# ChaiNEO_FrontConn_2x3.net
KiCad netlist of a schematic drawn in EAGLE
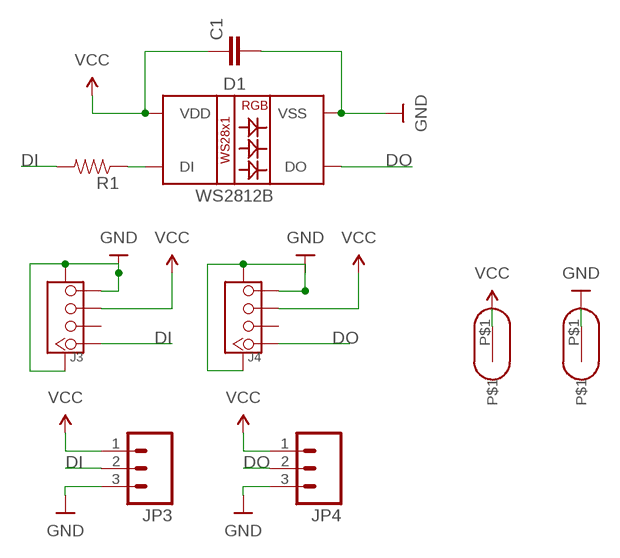
[diagram p0: schematic, sheet 1]

(export (version "E")
  (design (tool "Eeschema 10.0.6"))
  (components
    (comp (ref "C1")
      (value "CAP0603-CAP")
      (footprint "eagle-import:0603-CAP")
      (libsource (lib "eagle-import") (part "CAP0603-CAP"))
    )
    (comp (ref "D1")
      (value "WS2812B")
      (footprint "eagle-import:WS2812B")
      (libsource (lib "eagle-import") (part "WS2812B"))
    )
    (comp (ref "J3")
      (value "TWIG-4P-2.0-SMD-FEMALE-REINFORCE90D")
      (footprint "eagle-import:4P-SMD-2.0-90D")
      (libsource (lib "eagle-import") (part "TWIG-4P-2.0-SMD-FEMALE-REINFORCE90D"))
    )
    (comp (ref "J4")
      (value "TWIG-4P-2.0-SMD-FEMALE-REINFORCE90D")
      (footprint "eagle-import:4P-SMD-2.0-90D")
      (libsource (lib "eagle-import") (part "TWIG-4P-2.0-SMD-FEMALE-REINFORCE90D"))
    )
    (comp (ref "JP3")
      (value "M03LONGPADS")
      (footprint "eagle-import:1X03_LONGPADS")
      (libsource (lib "eagle-import") (part "M03LONGPADS"))
    )
    (comp (ref "JP4")
      (value "M03LONGPADS")
      (footprint "eagle-import:1X03_LONGPADS")
      (libsource (lib "eagle-import") (part "M03LONGPADS"))
    )
    (comp (ref "R1")
      (value "RESISTOR0603-RES")
      (footprint "eagle-import:0603-RES")
      (libsource (lib "eagle-import") (part "RESISTOR0603-RES"))
    )
    (comp (ref "U$7")
      (value "PLATED_TIE_MOUNT")
      (footprint "eagle-import:PLATED_TIE_MOUNT")
      (libsource (lib "eagle-import") (part "PLATED_TIE_MOUNT"))
    )
    (comp (ref "U$8")
      (value "PLATED_TIE_MOUNT")
      (footprint "eagle-import:PLATED_TIE_MOUNT")
      (libsource (lib "eagle-import") (part "PLATED_TIE_MOUNT"))
    )
  )
  (nets
    (net (code "1") (name "/DI") (class "Default")
      (node (ref "J3") (pin "1") (pinfunction "1_1") (pintype "bidirectional"))
      (node (ref "JP3") (pin "2") (pinfunction "2_2") (pintype "passive"))
      (node (ref "R1") (pin "2") (pinfunction "2_2") (pintype "passive"))
    )
    (net (code "2") (name "/DO") (class "Default")
      (node (ref "D1") (pin "2") (pinfunction "DO_2") (pintype "bidirectional"))
      (node (ref "J4") (pin "1") (pinfunction "1_1") (pintype "bidirectional"))
      (node (ref "JP4") (pin "2") (pinfunction "2_2") (pintype "passive"))
    )
    (net (code "3") (name "GND") (class "Default")
      (node (ref "C1") (pin "2") (pinfunction "2_2") (pintype "passive"))
      (node (ref "D1") (pin "3") (pinfunction "VSS_3") (pintype "bidirectional"))
      (node (ref "J3") (pin "4") (pinfunction "4_4") (pintype "bidirectional"))
      (node (ref "J3") (pin "SS1") (pinfunction "SS1_SS1") (pintype "bidirectional"))
      (node (ref "J3") (pin "SS2") (pinfunction "SS2_SS2") (pintype "bidirectional"))
      (node (ref "J4") (pin "4") (pinfunction "4_4") (pintype "bidirectional"))
      (node (ref "J4") (pin "SS1") (pinfunction "SS1_SS1") (pintype "bidirectional"))
      (node (ref "J4") (pin "SS2") (pinfunction "SS2_SS2") (pintype "bidirectional"))
      (node (ref "JP3") (pin "3") (pinfunction "3_3") (pintype "passive"))
      (node (ref "JP4") (pin "3") (pinfunction "3_3") (pintype "passive"))
      (node (ref "U$8") (pin "P$1") (pinfunction "P$1_P$1") (pintype "bidirectional"))
    )
    (net (code "4") (name "Net-(D1-DI)") (class "Default")
      (node (ref "D1") (pin "4") (pinfunction "DI_4") (pintype "bidirectional"))
      (node (ref "R1") (pin "1") (pinfunction "1_1") (pintype "passive"))
    )
    (net (code "5") (name "VCC") (class "Default")
      (node (ref "C1") (pin "1") (pinfunction "1_1") (pintype "passive"))
      (node (ref "D1") (pin "1") (pinfunction "VDD_1") (pintype "bidirectional"))
      (node (ref "J3") (pin "3") (pinfunction "3_3") (pintype "bidirectional"))
      (node (ref "J4") (pin "3") (pinfunction "3_3") (pintype "bidirectional"))
      (node (ref "JP3") (pin "1") (pinfunction "1_1") (pintype "passive"))
      (node (ref "JP4") (pin "1") (pinfunction "1_1") (pintype "passive"))
      (node (ref "U$7") (pin "P$1") (pinfunction "P$1_P$1") (pintype "bidirectional"))
    )
    (net (code "6") (name "unconnected-(J3-Pad2)") (class "Default")
      (node (ref "J3") (pin "2") (pinfunction "2_2") (pintype "bidirectional"))
    )
    (net (code "7") (name "unconnected-(J4-Pad2)") (class "Default")
      (node (ref "J4") (pin "2") (pinfunction "2_2") (pintype "bidirectional"))
    )
  )
)
